# 14A-005.net
KiCad netlist of a schematic drawn in EAGLE
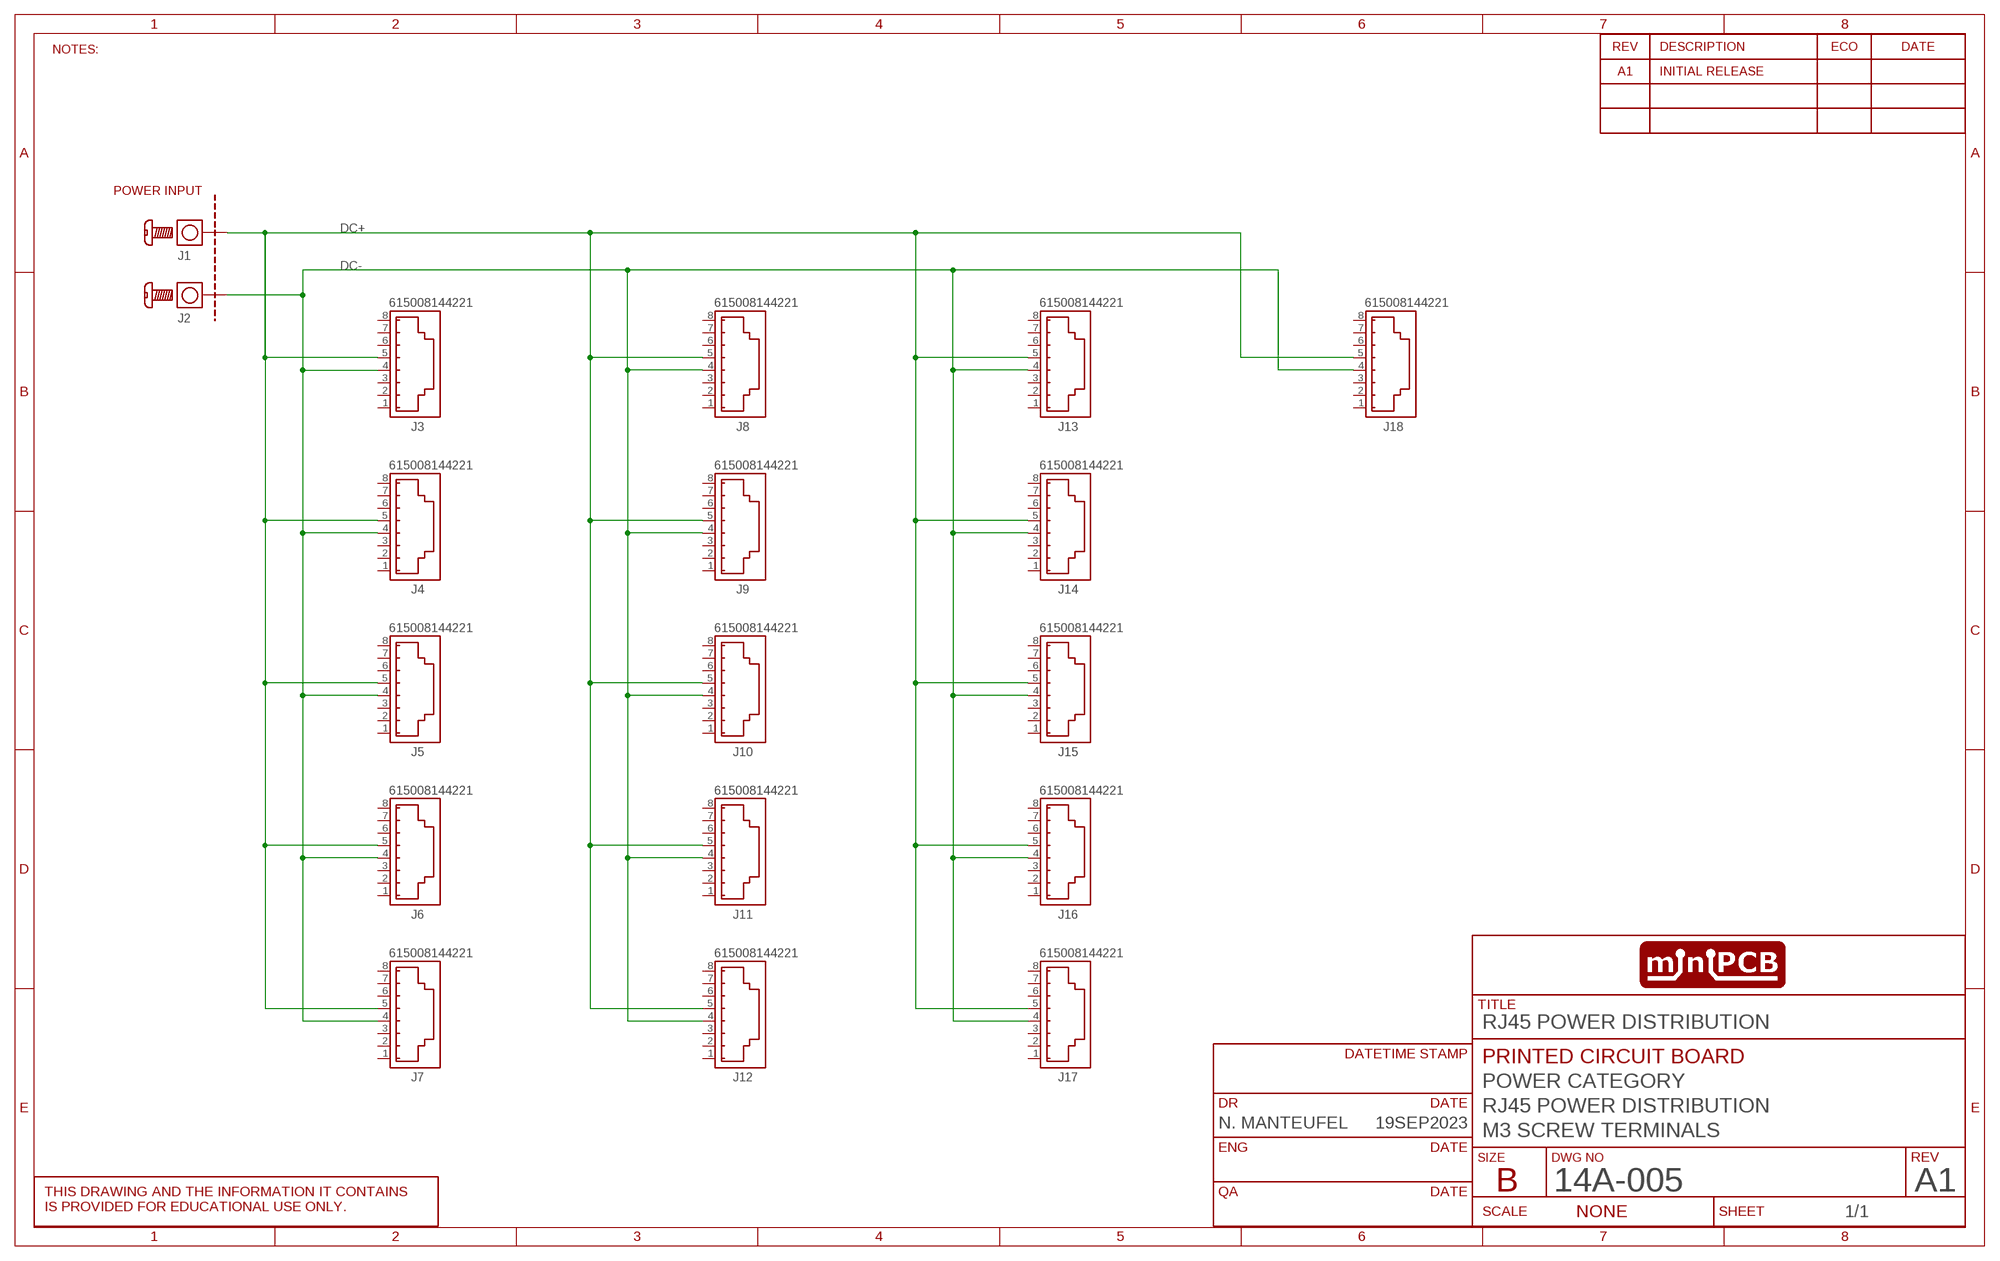
[diagram p0: schematic, sheet 1]

(export (version "E")
  (design (tool "Eeschema 10.0.6"))
  (components
    (comp (ref "-")
      (value "POWER INPUT")
      (footprint "eagle-import:MINIPCB_DOCK_100X100")
      (fields (field (name "NAME1") "RJ45 POWER DISTRIBUTION") (field (name "PART_NUMBER") "14A-005"))
      (libsource (lib "eagle-import") (part "MINIPCB_0P100X100"))
    )
    (comp (ref "J1")
      (value "SCREW-TERMINAL")
      (footprint "eagle-import:SCREW-TERMINAL-M3")
      (libsource (lib "eagle-import") (part "SCREW-TERMINAL"))
    )
    (comp (ref "J2")
      (value "SCREW-TERMINAL")
      (footprint "eagle-import:SCREW-TERMINAL-M3")
      (libsource (lib "eagle-import") (part "SCREW-TERMINAL"))
    )
    (comp (ref "J3")
      (value "615008144221")
      (footprint "eagle-import:615008144221")
      (libsource (lib "eagle-import") (part "615008144221"))
    )
    (comp (ref "J4")
      (value "615008144221")
      (footprint "eagle-import:615008144221")
      (libsource (lib "eagle-import") (part "615008144221"))
    )
    (comp (ref "J5")
      (value "615008144221")
      (footprint "eagle-import:615008144221")
      (libsource (lib "eagle-import") (part "615008144221"))
    )
    (comp (ref "J6")
      (value "615008144221")
      (footprint "eagle-import:615008144221")
      (libsource (lib "eagle-import") (part "615008144221"))
    )
    (comp (ref "J7")
      (value "615008144221")
      (footprint "eagle-import:615008144221")
      (libsource (lib "eagle-import") (part "615008144221"))
    )
    (comp (ref "J8")
      (value "615008144221")
      (footprint "eagle-import:615008144221")
      (libsource (lib "eagle-import") (part "615008144221"))
    )
    (comp (ref "J9")
      (value "615008144221")
      (footprint "eagle-import:615008144221")
      (libsource (lib "eagle-import") (part "615008144221"))
    )
    (comp (ref "J10")
      (value "615008144221")
      (footprint "eagle-import:615008144221")
      (libsource (lib "eagle-import") (part "615008144221"))
    )
    (comp (ref "J11")
      (value "615008144221")
      (footprint "eagle-import:615008144221")
      (libsource (lib "eagle-import") (part "615008144221"))
    )
    (comp (ref "J12")
      (value "615008144221")
      (footprint "eagle-import:615008144221")
      (libsource (lib "eagle-import") (part "615008144221"))
    )
    (comp (ref "J13")
      (value "615008144221")
      (footprint "eagle-import:615008144221")
      (libsource (lib "eagle-import") (part "615008144221"))
    )
    (comp (ref "J14")
      (value "615008144221")
      (footprint "eagle-import:615008144221")
      (libsource (lib "eagle-import") (part "615008144221"))
    )
    (comp (ref "J15")
      (value "615008144221")
      (footprint "eagle-import:615008144221")
      (libsource (lib "eagle-import") (part "615008144221"))
    )
    (comp (ref "J16")
      (value "615008144221")
      (footprint "eagle-import:615008144221")
      (libsource (lib "eagle-import") (part "615008144221"))
    )
    (comp (ref "J17")
      (value "615008144221")
      (footprint "eagle-import:615008144221")
      (libsource (lib "eagle-import") (part "615008144221"))
    )
    (comp (ref "J18")
      (value "615008144221")
      (footprint "eagle-import:615008144221")
      (libsource (lib "eagle-import") (part "615008144221"))
    )
  )
  (nets
    (net (code "1") (name "/DC+") (class "Default")
      (node (ref "J1") (pin "1") (pinfunction "1_1") (pintype "bidirectional"))
      (node (ref "J1") (pin "2") (pinfunction "1_2") (pintype "bidirectional"))
      (node (ref "J1") (pin "3") (pinfunction "1_3") (pintype "bidirectional"))
      (node (ref "J1") (pin "4") (pinfunction "1_4") (pintype "bidirectional"))
      (node (ref "J10") (pin "5") (pinfunction "4_5") (pintype "passive"))
      (node (ref "J11") (pin "5") (pinfunction "4_5") (pintype "passive"))
      (node (ref "J12") (pin "5") (pinfunction "4_5") (pintype "passive"))
      (node (ref "J13") (pin "5") (pinfunction "4_5") (pintype "passive"))
      (node (ref "J14") (pin "5") (pinfunction "4_5") (pintype "passive"))
      (node (ref "J15") (pin "5") (pinfunction "4_5") (pintype "passive"))
      (node (ref "J16") (pin "5") (pinfunction "4_5") (pintype "passive"))
      (node (ref "J17") (pin "5") (pinfunction "4_5") (pintype "passive"))
      (node (ref "J18") (pin "5") (pinfunction "4_5") (pintype "passive"))
      (node (ref "J3") (pin "5") (pinfunction "4_5") (pintype "passive"))
      (node (ref "J4") (pin "5") (pinfunction "4_5") (pintype "passive"))
      (node (ref "J5") (pin "5") (pinfunction "4_5") (pintype "passive"))
      (node (ref "J6") (pin "5") (pinfunction "4_5") (pintype "passive"))
      (node (ref "J7") (pin "5") (pinfunction "4_5") (pintype "passive"))
      (node (ref "J8") (pin "5") (pinfunction "4_5") (pintype "passive"))
      (node (ref "J9") (pin "5") (pinfunction "4_5") (pintype "passive"))
    )
    (net (code "2") (name "/DC-") (class "Default")
      (node (ref "J10") (pin "4") (pinfunction "5_4") (pintype "passive"))
      (node (ref "J11") (pin "4") (pinfunction "5_4") (pintype "passive"))
      (node (ref "J12") (pin "4") (pinfunction "5_4") (pintype "passive"))
      (node (ref "J13") (pin "4") (pinfunction "5_4") (pintype "passive"))
      (node (ref "J14") (pin "4") (pinfunction "5_4") (pintype "passive"))
      (node (ref "J15") (pin "4") (pinfunction "5_4") (pintype "passive"))
      (node (ref "J16") (pin "4") (pinfunction "5_4") (pintype "passive"))
      (node (ref "J17") (pin "4") (pinfunction "5_4") (pintype "passive"))
      (node (ref "J18") (pin "4") (pinfunction "5_4") (pintype "passive"))
      (node (ref "J2") (pin "1") (pinfunction "1_1") (pintype "bidirectional"))
      (node (ref "J2") (pin "2") (pinfunction "1_2") (pintype "bidirectional"))
      (node (ref "J2") (pin "3") (pinfunction "1_3") (pintype "bidirectional"))
      (node (ref "J2") (pin "4") (pinfunction "1_4") (pintype "bidirectional"))
      (node (ref "J3") (pin "4") (pinfunction "5_4") (pintype "passive"))
      (node (ref "J4") (pin "4") (pinfunction "5_4") (pintype "passive"))
      (node (ref "J5") (pin "4") (pinfunction "5_4") (pintype "passive"))
      (node (ref "J6") (pin "4") (pinfunction "5_4") (pintype "passive"))
      (node (ref "J7") (pin "4") (pinfunction "5_4") (pintype "passive"))
      (node (ref "J8") (pin "4") (pinfunction "5_4") (pintype "passive"))
      (node (ref "J9") (pin "4") (pinfunction "5_4") (pintype "passive"))
    )
    (net (code "3") (name "unconnected-(J3-1-Pad8)") (class "Default")
      (node (ref "J3") (pin "8") (pinfunction "1_8") (pintype "passive"))
    )
    (net (code "4") (name "unconnected-(J3-2-Pad7)") (class "Default")
      (node (ref "J3") (pin "7") (pinfunction "2_7") (pintype "passive"))
    )
    (net (code "5") (name "unconnected-(J3-3-Pad6)") (class "Default")
      (node (ref "J3") (pin "6") (pinfunction "3_6") (pintype "passive"))
    )
    (net (code "6") (name "unconnected-(J3-6-Pad3)") (class "Default")
      (node (ref "J3") (pin "3") (pinfunction "6_3") (pintype "passive"))
    )
    (net (code "7") (name "unconnected-(J3-7-Pad2)") (class "Default")
      (node (ref "J3") (pin "2") (pinfunction "7_2") (pintype "passive"))
    )
    (net (code "8") (name "unconnected-(J3-8-Pad1)") (class "Default")
      (node (ref "J3") (pin "1") (pinfunction "8_1") (pintype "passive"))
    )
    (net (code "9") (name "unconnected-(J4-1-Pad8)") (class "Default")
      (node (ref "J4") (pin "8") (pinfunction "1_8") (pintype "passive"))
    )
    (net (code "10") (name "unconnected-(J4-2-Pad7)") (class "Default")
      (node (ref "J4") (pin "7") (pinfunction "2_7") (pintype "passive"))
    )
    (net (code "11") (name "unconnected-(J4-3-Pad6)") (class "Default")
      (node (ref "J4") (pin "6") (pinfunction "3_6") (pintype "passive"))
    )
    (net (code "12") (name "unconnected-(J4-6-Pad3)") (class "Default")
      (node (ref "J4") (pin "3") (pinfunction "6_3") (pintype "passive"))
    )
    (net (code "13") (name "unconnected-(J4-7-Pad2)") (class "Default")
      (node (ref "J4") (pin "2") (pinfunction "7_2") (pintype "passive"))
    )
    (net (code "14") (name "unconnected-(J4-8-Pad1)") (class "Default")
      (node (ref "J4") (pin "1") (pinfunction "8_1") (pintype "passive"))
    )
    (net (code "15") (name "unconnected-(J5-1-Pad8)") (class "Default")
      (node (ref "J5") (pin "8") (pinfunction "1_8") (pintype "passive"))
    )
    (net (code "16") (name "unconnected-(J5-2-Pad7)") (class "Default")
      (node (ref "J5") (pin "7") (pinfunction "2_7") (pintype "passive"))
    )
    (net (code "17") (name "unconnected-(J5-3-Pad6)") (class "Default")
      (node (ref "J5") (pin "6") (pinfunction "3_6") (pintype "passive"))
    )
    (net (code "18") (name "unconnected-(J5-6-Pad3)") (class "Default")
      (node (ref "J5") (pin "3") (pinfunction "6_3") (pintype "passive"))
    )
    (net (code "19") (name "unconnected-(J5-7-Pad2)") (class "Default")
      (node (ref "J5") (pin "2") (pinfunction "7_2") (pintype "passive"))
    )
    (net (code "20") (name "unconnected-(J5-8-Pad1)") (class "Default")
      (node (ref "J5") (pin "1") (pinfunction "8_1") (pintype "passive"))
    )
    (net (code "21") (name "unconnected-(J6-1-Pad8)") (class "Default")
      (node (ref "J6") (pin "8") (pinfunction "1_8") (pintype "passive"))
    )
    (net (code "22") (name "unconnected-(J6-2-Pad7)") (class "Default")
      (node (ref "J6") (pin "7") (pinfunction "2_7") (pintype "passive"))
    )
    (net (code "23") (name "unconnected-(J6-3-Pad6)") (class "Default")
      (node (ref "J6") (pin "6") (pinfunction "3_6") (pintype "passive"))
    )
    (net (code "24") (name "unconnected-(J6-6-Pad3)") (class "Default")
      (node (ref "J6") (pin "3") (pinfunction "6_3") (pintype "passive"))
    )
    (net (code "25") (name "unconnected-(J6-7-Pad2)") (class "Default")
      (node (ref "J6") (pin "2") (pinfunction "7_2") (pintype "passive"))
    )
    (net (code "26") (name "unconnected-(J6-8-Pad1)") (class "Default")
      (node (ref "J6") (pin "1") (pinfunction "8_1") (pintype "passive"))
    )
    (net (code "27") (name "unconnected-(J7-1-Pad8)") (class "Default")
      (node (ref "J7") (pin "8") (pinfunction "1_8") (pintype "passive"))
    )
    (net (code "28") (name "unconnected-(J7-2-Pad7)") (class "Default")
      (node (ref "J7") (pin "7") (pinfunction "2_7") (pintype "passive"))
    )
    (net (code "29") (name "unconnected-(J7-3-Pad6)") (class "Default")
      (node (ref "J7") (pin "6") (pinfunction "3_6") (pintype "passive"))
    )
    (net (code "30") (name "unconnected-(J7-6-Pad3)") (class "Default")
      (node (ref "J7") (pin "3") (pinfunction "6_3") (pintype "passive"))
    )
    (net (code "31") (name "unconnected-(J7-7-Pad2)") (class "Default")
      (node (ref "J7") (pin "2") (pinfunction "7_2") (pintype "passive"))
    )
    (net (code "32") (name "unconnected-(J7-8-Pad1)") (class "Default")
      (node (ref "J7") (pin "1") (pinfunction "8_1") (pintype "passive"))
    )
    (net (code "33") (name "unconnected-(J8-1-Pad8)") (class "Default")
      (node (ref "J8") (pin "8") (pinfunction "1_8") (pintype "passive"))
    )
    (net (code "34") (name "unconnected-(J8-2-Pad7)") (class "Default")
      (node (ref "J8") (pin "7") (pinfunction "2_7") (pintype "passive"))
    )
    (net (code "35") (name "unconnected-(J8-3-Pad6)") (class "Default")
      (node (ref "J8") (pin "6") (pinfunction "3_6") (pintype "passive"))
    )
    (net (code "36") (name "unconnected-(J8-6-Pad3)") (class "Default")
      (node (ref "J8") (pin "3") (pinfunction "6_3") (pintype "passive"))
    )
    (net (code "37") (name "unconnected-(J8-7-Pad2)") (class "Default")
      (node (ref "J8") (pin "2") (pinfunction "7_2") (pintype "passive"))
    )
    (net (code "38") (name "unconnected-(J8-8-Pad1)") (class "Default")
      (node (ref "J8") (pin "1") (pinfunction "8_1") (pintype "passive"))
    )
    (net (code "39") (name "unconnected-(J9-1-Pad8)") (class "Default")
      (node (ref "J9") (pin "8") (pinfunction "1_8") (pintype "passive"))
    )
    (net (code "40") (name "unconnected-(J9-2-Pad7)") (class "Default")
      (node (ref "J9") (pin "7") (pinfunction "2_7") (pintype "passive"))
    )
    (net (code "41") (name "unconnected-(J9-3-Pad6)") (class "Default")
      (node (ref "J9") (pin "6") (pinfunction "3_6") (pintype "passive"))
    )
    (net (code "42") (name "unconnected-(J9-6-Pad3)") (class "Default")
      (node (ref "J9") (pin "3") (pinfunction "6_3") (pintype "passive"))
    )
    (net (code "43") (name "unconnected-(J9-7-Pad2)") (class "Default")
      (node (ref "J9") (pin "2") (pinfunction "7_2") (pintype "passive"))
    )
    (net (code "44") (name "unconnected-(J9-8-Pad1)") (class "Default")
      (node (ref "J9") (pin "1") (pinfunction "8_1") (pintype "passive"))
    )
    (net (code "45") (name "unconnected-(J10-1-Pad8)") (class "Default")
      (node (ref "J10") (pin "8") (pinfunction "1_8") (pintype "passive"))
    )
    (net (code "46") (name "unconnected-(J10-2-Pad7)") (class "Default")
      (node (ref "J10") (pin "7") (pinfunction "2_7") (pintype "passive"))
    )
    (net (code "47") (name "unconnected-(J10-3-Pad6)") (class "Default")
      (node (ref "J10") (pin "6") (pinfunction "3_6") (pintype "passive"))
    )
    (net (code "48") (name "unconnected-(J10-6-Pad3)") (class "Default")
      (node (ref "J10") (pin "3") (pinfunction "6_3") (pintype "passive"))
    )
    (net (code "49") (name "unconnected-(J10-7-Pad2)") (class "Default")
      (node (ref "J10") (pin "2") (pinfunction "7_2") (pintype "passive"))
    )
    (net (code "50") (name "unconnected-(J10-8-Pad1)") (class "Default")
      (node (ref "J10") (pin "1") (pinfunction "8_1") (pintype "passive"))
    )
    (net (code "51") (name "unconnected-(J11-1-Pad8)") (class "Default")
      (node (ref "J11") (pin "8") (pinfunction "1_8") (pintype "passive"))
    )
    (net (code "52") (name "unconnected-(J11-2-Pad7)") (class "Default")
      (node (ref "J11") (pin "7") (pinfunction "2_7") (pintype "passive"))
    )
    (net (code "53") (name "unconnected-(J11-3-Pad6)") (class "Default")
      (node (ref "J11") (pin "6") (pinfunction "3_6") (pintype "passive"))
    )
    (net (code "54") (name "unconnected-(J11-6-Pad3)") (class "Default")
      (node (ref "J11") (pin "3") (pinfunction "6_3") (pintype "passive"))
    )
    (net (code "55") (name "unconnected-(J11-7-Pad2)") (class "Default")
      (node (ref "J11") (pin "2") (pinfunction "7_2") (pintype "passive"))
    )
    (net (code "56") (name "unconnected-(J11-8-Pad1)") (class "Default")
      (node (ref "J11") (pin "1") (pinfunction "8_1") (pintype "passive"))
    )
    (net (code "57") (name "unconnected-(J12-1-Pad8)") (class "Default")
      (node (ref "J12") (pin "8") (pinfunction "1_8") (pintype "passive"))
    )
    (net (code "58") (name "unconnected-(J12-2-Pad7)") (class "Default")
      (node (ref "J12") (pin "7") (pinfunction "2_7") (pintype "passive"))
    )
    (net (code "59") (name "unconnected-(J12-3-Pad6)") (class "Default")
      (node (ref "J12") (pin "6") (pinfunction "3_6") (pintype "passive"))
    )
    (net (code "60") (name "unconnected-(J12-6-Pad3)") (class "Default")
      (node (ref "J12") (pin "3") (pinfunction "6_3") (pintype "passive"))
    )
    (net (code "61") (name "unconnected-(J12-7-Pad2)") (class "Default")
      (node (ref "J12") (pin "2") (pinfunction "7_2") (pintype "passive"))
    )
    (net (code "62") (name "unconnected-(J12-8-Pad1)") (class "Default")
      (node (ref "J12") (pin "1") (pinfunction "8_1") (pintype "passive"))
    )
    (net (code "63") (name "unconnected-(J13-1-Pad8)") (class "Default")
      (node (ref "J13") (pin "8") (pinfunction "1_8") (pintype "passive"))
    )
    (net (code "64") (name "unconnected-(J13-2-Pad7)") (class "Default")
      (node (ref "J13") (pin "7") (pinfunction "2_7") (pintype "passive"))
    )
    (net (code "65") (name "unconnected-(J13-3-Pad6)") (class "Default")
      (node (ref "J13") (pin "6") (pinfunction "3_6") (pintype "passive"))
    )
    (net (code "66") (name "unconnected-(J13-6-Pad3)") (class "Default")
      (node (ref "J13") (pin "3") (pinfunction "6_3") (pintype "passive"))
    )
    (net (code "67") (name "unconnected-(J13-7-Pad2)") (class "Default")
      (node (ref "J13") (pin "2") (pinfunction "7_2") (pintype "passive"))
    )
    (net (code "68") (name "unconnected-(J13-8-Pad1)") (class "Default")
      (node (ref "J13") (pin "1") (pinfunction "8_1") (pintype "passive"))
    )
    (net (code "69") (name "unconnected-(J14-1-Pad8)") (class "Default")
      (node (ref "J14") (pin "8") (pinfunction "1_8") (pintype "passive"))
    )
    (net (code "70") (name "unconnected-(J14-2-Pad7)") (class "Default")
      (node (ref "J14") (pin "7") (pinfunction "2_7") (pintype "passive"))
    )
    (net (code "71") (name "unconnected-(J14-3-Pad6)") (class "Default")
      (node (ref "J14") (pin "6") (pinfunction "3_6") (pintype "passive"))
    )
    (net (code "72") (name "unconnected-(J14-6-Pad3)") (class "Default")
      (node (ref "J14") (pin "3") (pinfunction "6_3") (pintype "passive"))
    )
    (net (code "73") (name "unconnected-(J14-7-Pad2)") (class "Default")
      (node (ref "J14") (pin "2") (pinfunction "7_2") (pintype "passive"))
    )
    (net (code "74") (name "unconnected-(J14-8-Pad1)") (class "Default")
      (node (ref "J14") (pin "1") (pinfunction "8_1") (pintype "passive"))
    )
    (net (code "75") (name "unconnected-(J15-1-Pad8)") (class "Default")
      (node (ref "J15") (pin "8") (pinfunction "1_8") (pintype "passive"))
    )
    (net (code "76") (name "unconnected-(J15-2-Pad7)") (class "Default")
      (node (ref "J15") (pin "7") (pinfunction "2_7") (pintype "passive"))
    )
    (net (code "77") (name "unconnected-(J15-3-Pad6)") (class "Default")
      (node (ref "J15") (pin "6") (pinfunction "3_6") (pintype "passive"))
    )
    (net (code "78") (name "unconnected-(J15-6-Pad3)") (class "Default")
      (node (ref "J15") (pin "3") (pinfunction "6_3") (pintype "passive"))
    )
    (net (code "79") (name "unconnected-(J15-7-Pad2)") (class "Default")
      (node (ref "J15") (pin "2") (pinfunction "7_2") (pintype "passive"))
    )
    (net (code "80") (name "unconnected-(J15-8-Pad1)") (class "Default")
      (node (ref "J15") (pin "1") (pinfunction "8_1") (pintype "passive"))
    )
    (net (code "81") (name "unconnected-(J16-1-Pad8)") (class "Default")
      (node (ref "J16") (pin "8") (pinfunction "1_8") (pintype "passive"))
    )
    (net (code "82") (name "unconnected-(J16-2-Pad7)") (class "Default")
      (node (ref "J16") (pin "7") (pinfunction "2_7") (pintype "passive"))
    )
    (net (code "83") (name "unconnected-(J16-3-Pad6)") (class "Default")
      (node (ref "J16") (pin "6") (pinfunction "3_6") (pintype "passive"))
    )
    (net (code "84") (name "unconnected-(J16-6-Pad3)") (class "Default")
      (node (ref "J16") (pin "3") (pinfunction "6_3") (pintype "passive"))
    )
    (net (code "85") (name "unconnected-(J16-7-Pad2)") (class "Default")
      (node (ref "J16") (pin "2") (pinfunction "7_2") (pintype "passive"))
    )
    (net (code "86") (name "unconnected-(J16-8-Pad1)") (class "Default")
      (node (ref "J16") (pin "1") (pinfunction "8_1") (pintype "passive"))
    )
    (net (code "87") (name "unconnected-(J17-1-Pad8)") (class "Default")
      (node (ref "J17") (pin "8") (pinfunction "1_8") (pintype "passive"))
    )
    (net (code "88") (name "unconnected-(J17-2-Pad7)") (class "Default")
      (node (ref "J17") (pin "7") (pinfunction "2_7") (pintype "passive"))
    )
    (net (code "89") (name "unconnected-(J17-3-Pad6)") (class "Default")
      (node (ref "J17") (pin "6") (pinfunction "3_6") (pintype "passive"))
    )
    (net (code "90") (name "unconnected-(J17-6-Pad3)") (class "Default")
      (node (ref "J17") (pin "3") (pinfunction "6_3") (pintype "passive"))
    )
    (net (code "91") (name "unconnected-(J17-7-Pad2)") (class "Default")
      (node (ref "J17") (pin "2") (pinfunction "7_2") (pintype "passive"))
    )
    (net (code "92") (name "unconnected-(J17-8-Pad1)") (class "Default")
      (node (ref "J17") (pin "1") (pinfunction "8_1") (pintype "passive"))
    )
    (net (code "93") (name "unconnected-(J18-1-Pad8)") (class "Default")
      (node (ref "J18") (pin "8") (pinfunction "1_8") (pintype "passive"))
    )
    (net (code "94") (name "unconnected-(J18-2-Pad7)") (class "Default")
      (node (ref "J18") (pin "7") (pinfunction "2_7") (pintype "passive"))
    )
    (net (code "95") (name "unconnected-(J18-3-Pad6)") (class "Default")
      (node (ref "J18") (pin "6") (pinfunction "3_6") (pintype "passive"))
    )
    (net (code "96") (name "unconnected-(J18-6-Pad3)") (class "Default")
      (node (ref "J18") (pin "3") (pinfunction "6_3") (pintype "passive"))
    )
    (net (code "97") (name "unconnected-(J18-7-Pad2)") (class "Default")
      (node (ref "J18") (pin "2") (pinfunction "7_2") (pintype "passive"))
    )
    (net (code "98") (name "unconnected-(J18-8-Pad1)") (class "Default")
      (node (ref "J18") (pin "1") (pinfunction "8_1") (pintype "passive"))
    )
  )
)
